# chain.net
KiCad netlist of a schematic drawn in EAGLE
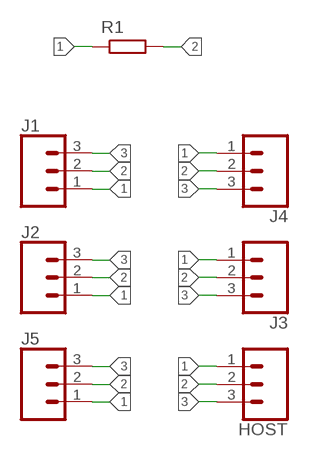
[diagram p0: schematic, sheet 1]

(export (version "E")
  (design (tool "Eeschema 10.0.6"))
  (components
    (comp (ref "HOST")
      (value "CONN_03LONGPADS")
      (footprint "eagle-import:1X03_LONGPADS")
      (libsource (lib "eagle-import") (part "CONN_03LONGPADS"))
    )
    (comp (ref "J1")
      (value "CONN_03LONGPADS")
      (footprint "eagle-import:1X03_LONGPADS")
      (libsource (lib "eagle-import") (part "CONN_03LONGPADS"))
    )
    (comp (ref "J2")
      (value "CONN_03LONGPADS")
      (footprint "eagle-import:1X03_LONGPADS")
      (libsource (lib "eagle-import") (part "CONN_03LONGPADS"))
    )
    (comp (ref "J3")
      (value "CONN_03LONGPADS")
      (footprint "eagle-import:1X03_LONGPADS")
      (libsource (lib "eagle-import") (part "CONN_03LONGPADS"))
    )
    (comp (ref "J4")
      (value "CONN_03LONGPADS")
      (footprint "eagle-import:1X03_LONGPADS")
      (libsource (lib "eagle-import") (part "CONN_03LONGPADS"))
    )
    (comp (ref "J5")
      (value "CONN_03LONGPADS")
      (footprint "eagle-import:1X03_LONGPADS")
      (libsource (lib "eagle-import") (part "CONN_03LONGPADS"))
    )
    (comp (ref "R1")
      (value "RESISTOR0603-N")
      (footprint "eagle-import:R0603-N")
      (libsource (lib "eagle-import") (part "RESISTOR0603-N"))
    )
  )
  (nets
    (net (code "1") (name "1") (class "Default")
      (node (ref "HOST") (pin "1") (pinfunction "1_1") (pintype "passive"))
      (node (ref "J1") (pin "1") (pinfunction "1_1") (pintype "passive"))
      (node (ref "J2") (pin "1") (pinfunction "1_1") (pintype "passive"))
      (node (ref "J3") (pin "1") (pinfunction "1_1") (pintype "passive"))
      (node (ref "J4") (pin "1") (pinfunction "1_1") (pintype "passive"))
      (node (ref "J5") (pin "1") (pinfunction "1_1") (pintype "passive"))
      (node (ref "R1") (pin "1") (pinfunction "P$1_1") (pintype "passive"))
    )
    (net (code "2") (name "2") (class "Default")
      (node (ref "HOST") (pin "2") (pinfunction "2_2") (pintype "passive"))
      (node (ref "J1") (pin "2") (pinfunction "2_2") (pintype "passive"))
      (node (ref "J2") (pin "2") (pinfunction "2_2") (pintype "passive"))
      (node (ref "J3") (pin "2") (pinfunction "2_2") (pintype "passive"))
      (node (ref "J4") (pin "2") (pinfunction "2_2") (pintype "passive"))
      (node (ref "J5") (pin "2") (pinfunction "2_2") (pintype "passive"))
      (node (ref "R1") (pin "2") (pinfunction "P$2_2") (pintype "passive"))
    )
    (net (code "3") (name "3") (class "Default")
      (node (ref "HOST") (pin "3") (pinfunction "3_3") (pintype "passive"))
      (node (ref "J1") (pin "3") (pinfunction "3_3") (pintype "passive"))
      (node (ref "J2") (pin "3") (pinfunction "3_3") (pintype "passive"))
      (node (ref "J3") (pin "3") (pinfunction "3_3") (pintype "passive"))
      (node (ref "J4") (pin "3") (pinfunction "3_3") (pintype "passive"))
      (node (ref "J5") (pin "3") (pinfunction "3_3") (pintype "passive"))
    )
  )
)
